# amphenol_npa201.net
KiCad netlist of a schematic drawn in EAGLE
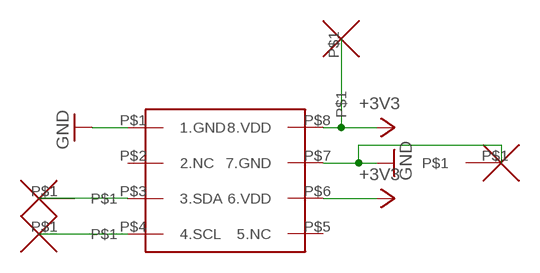
[diagram p0: schematic, sheet 1]

(export (version "E")
  (design (tool "Eeschema 10.0.6"))
  (components
    (comp (ref "U$1")
      (value "AMPHENOL_NPA201")
      (footprint "eagle-import:AMPHENOL_NPA201")
      (libsource (lib "eagle-import") (part "AMPHENOL_NPA201"))
    )
    (comp (ref "U$2")
      (value "WIREPAD_0,8/0,45")
      (footprint "eagle-import:WIREPAD_0,8_0,45")
      (libsource (lib "eagle-import") (part "WIREPAD_0,8/0,45"))
    )
    (comp (ref "U$3")
      (value "WIREPAD_0,8/0,45")
      (footprint "eagle-import:WIREPAD_0,8_0,45")
      (libsource (lib "eagle-import") (part "WIREPAD_0,8/0,45"))
    )
    (comp (ref "U$4")
      (value "WIREPAD_0,8/0,45")
      (footprint "eagle-import:WIREPAD_0,8_0,45")
      (libsource (lib "eagle-import") (part "WIREPAD_0,8/0,45"))
    )
    (comp (ref "U$5")
      (value "WIREPAD_0,8/0,45")
      (footprint "eagle-import:WIREPAD_0,8_0,45")
      (libsource (lib "eagle-import") (part "WIREPAD_0,8/0,45"))
    )
  )
  (nets
    (net (code "1") (name "+3V3") (class "Default")
      (node (ref "U$1") (pin "P$6") (pinfunction "6.VDD_P$6") (pintype "bidirectional"))
      (node (ref "U$1") (pin "P$8") (pinfunction "8.VDD_P$8") (pintype "bidirectional"))
      (node (ref "U$4") (pin "P$1") (pinfunction "P$1_P$1") (pintype "bidirectional"))
    )
    (net (code "2") (name "GND") (class "Default")
      (node (ref "U$1") (pin "P$1") (pinfunction "1.GND_P$1") (pintype "bidirectional"))
      (node (ref "U$1") (pin "P$7") (pinfunction "7.GND_P$7") (pintype "bidirectional"))
      (node (ref "U$5") (pin "P$1") (pinfunction "P$1_P$1") (pintype "bidirectional"))
    )
    (net (code "3") (name "Net-(U$1-3.SDA)") (class "Default")
      (node (ref "U$1") (pin "P$3") (pinfunction "3.SDA_P$3") (pintype "bidirectional"))
      (node (ref "U$2") (pin "P$1") (pinfunction "P$1_P$1") (pintype "bidirectional"))
    )
    (net (code "4") (name "Net-(U$1-4.SCL)") (class "Default")
      (node (ref "U$1") (pin "P$4") (pinfunction "4.SCL_P$4") (pintype "bidirectional"))
      (node (ref "U$3") (pin "P$1") (pinfunction "P$1_P$1") (pintype "bidirectional"))
    )
    (net (code "5") (name "unconnected-(U$1-2.NC-PadP$2)") (class "Default")
      (node (ref "U$1") (pin "P$2") (pinfunction "2.NC_P$2") (pintype "bidirectional"))
    )
    (net (code "6") (name "unconnected-(U$1-5.NC-PadP$5)") (class "Default")
      (node (ref "U$1") (pin "P$5") (pinfunction "5.NC_P$5") (pintype "bidirectional"))
    )
  )
)
